# io.net
KiCad netlist of a schematic drawn in Altium Designer
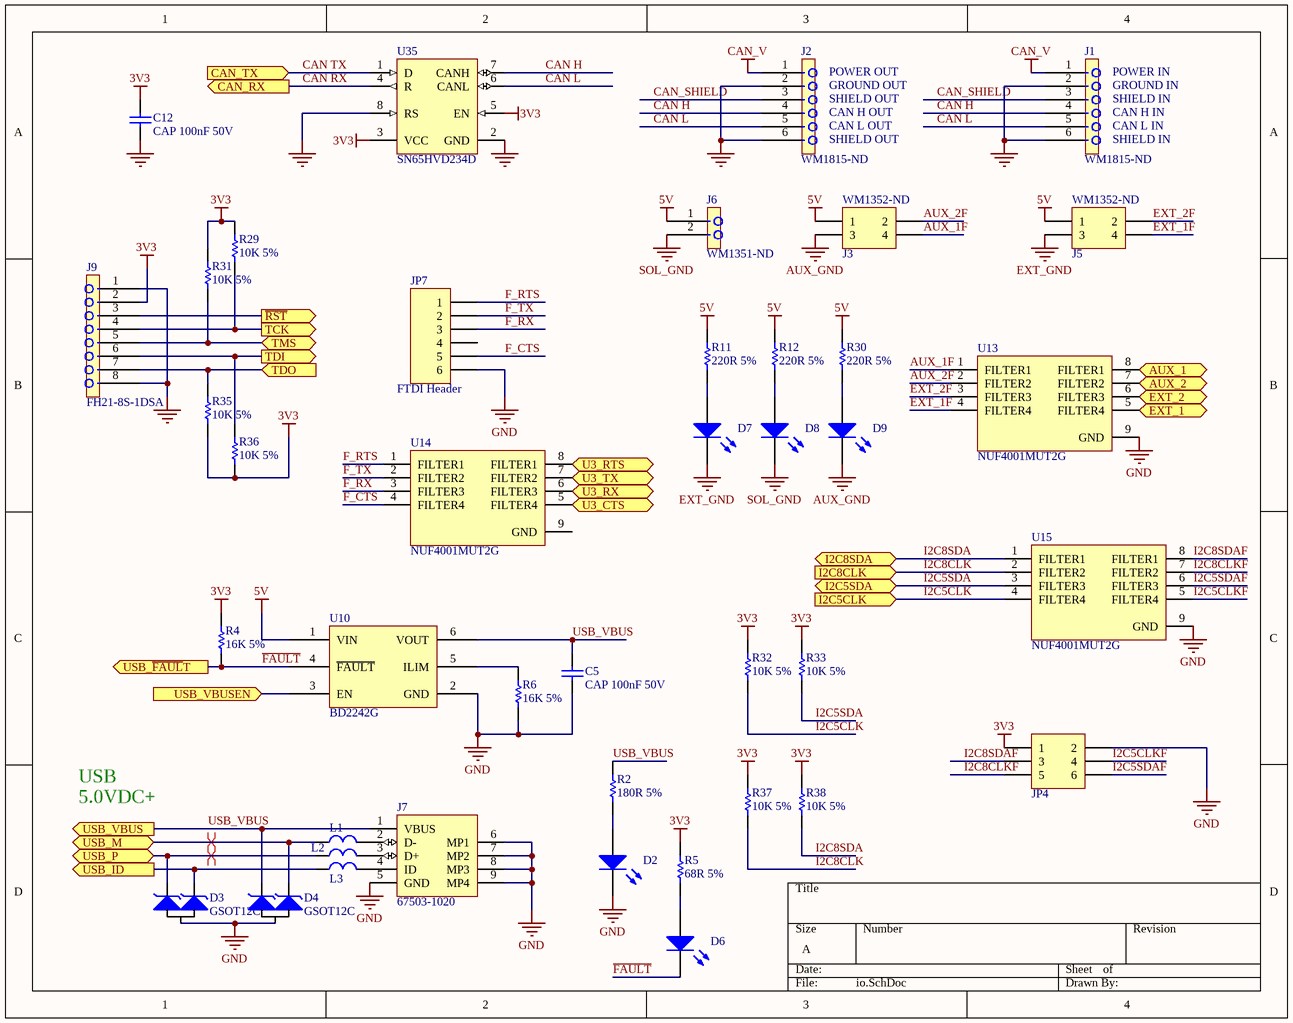
[diagram p0: io.SchDoc]

(export (version "E")
  (design (tool "Eeschema 10.0.6"))
  (components
    (comp (ref "C5")
      (value "CAP 100nF 50V")
      (footprint "CAPC0603(1608)100_M")
      (description "CAP 100nF 50V Â±0.1pF 0603 (1608 Metric) Thickness 1mm SMD")
      (fields (field (name "TOLERANCE") "Â±0.1pF"))
      (libsource (lib "Altium Content Vault") (part "CMP-1035-00010-1"))
    )
    (comp (ref "C12")
      (value "CAP 100nF 50V")
      (footprint "CAPC0603(1608)100_M")
      (description "CAP 100nF 50V Â±0.1pF 0603 (1608 Metric) Thickness 1mm SMD")
      (fields (field (name "TOLERANCE") "Â±0.1pF"))
      (libsource (lib "Altium Content Vault") (part "CMP-1035-00010-1"))
    )
    (comp (ref "D2")
      (value "LED")
      (footprint "LED-0603")
      (description "Typical RED, GREEN, YELLOW, AMBER GaAs LED")
      (fields (field (name "PUBLISHER") "Altium Limited"))
      (libsource (lib "HSBNE-Vend") (part "LED"))
    )
    (comp (ref "D3")
      (value "GSOT12C")
      (footprint "SOT-23 - ESD")
      (description "DIO GSOT12C ESD 2LINE 12V SOT23")
      (fields (field (name "MPN") "GSOT12C-E3-08"))
      (libsource (lib "HSBNE-Vend") (part "2749"))
    )
    (comp (ref "D4")
      (value "GSOT12C")
      (footprint "SOT-23 - ESD")
      (description "DIO GSOT12C ESD 2LINE 12V SOT23")
      (fields (field (name "MPN") "GSOT12C-E3-08"))
      (libsource (lib "HSBNE-Vend") (part "2749"))
    )
    (comp (ref "D6")
      (value "LED")
      (footprint "LED-0603")
      (description "Typical RED, GREEN, YELLOW, AMBER GaAs LED")
      (fields (field (name "PUBLISHER") "Altium Limited"))
      (libsource (lib "HSBNE-Vend") (part "LED"))
    )
    (comp (ref "D7")
      (value "LED")
      (footprint "LED-0603")
      (description "Typical RED, GREEN, YELLOW, AMBER GaAs LED")
      (fields (field (name "PUBLISHER") "Altium Limited"))
      (libsource (lib "HSBNE-Vend") (part "LED"))
    )
    (comp (ref "D8")
      (value "LED")
      (footprint "LED-0603")
      (description "Typical RED, GREEN, YELLOW, AMBER GaAs LED")
      (fields (field (name "PUBLISHER") "Altium Limited"))
      (libsource (lib "HSBNE-Vend") (part "LED"))
    )
    (comp (ref "D9")
      (value "LED")
      (footprint "LED-0603")
      (description "Typical RED, GREEN, YELLOW, AMBER GaAs LED")
      (fields (field (name "PUBLISHER") "Altium Limited"))
      (libsource (lib "HSBNE-Vend") (part "LED"))
    )
    (comp (ref "J1") (value "WM1815-ND") (footprint "M43045H-6") (libsource (lib "HSBNE-Vend") (part "CON6")))
    (comp (ref "J2") (value "WM1815-ND") (footprint "M43045H-6") (libsource (lib "HSBNE-Vend") (part "CON6")))
    (comp (ref "J3")
      (value "Header 2x2 2.54mm")
      (footprint "Molex 39-30-1040")
      (description "Header, 4-Pin")
      (fields (field (name "SUPPLIER PART NUMBER 1") "WM1352-ND"))
      (libsource (lib "HSBNE-Vend") (part "Header 2x2"))
    )
    (comp (ref "J5")
      (value "Header 2x2 2.54mm")
      (footprint "Molex 39-30-1040")
      (description "Header, 4-Pin")
      (fields (field (name "SUPPLIER PART NUMBER 1") "WM1352-ND"))
      (libsource (lib "HSBNE-Vend") (part "Header 2x2"))
    )
    (comp (ref "J6")
      (value "WM1351-ND")
      (footprint "M5569-2")
      (description "6.35mm right-angle 90° male spade terminal PCB mount")
      (libsource (lib "HSBNE-Vend") (part "CON2"))
    )
    (comp (ref "J7")
      (value "67503-1020")
      (footprint "MOLX-67503-1020_V")
      (description "USB, MINI, SMD, RA KME04-USBMU03A01")
      (fields (field (name "MANUFACTURER") "Molex"))
      (libsource (lib "Altium Content Vault") (part "MOLX-67503-1020"))
    )
    (comp (ref "J9")
      (value "FH21-8S-1DSA")
      (footprint "FH21-8S-1DSA")
      (libsource (lib "HSBNE-Vend") (part "CON8"))
    )
    (comp (ref "JP4")
      (value "Header 3x2 2.54mm")
      (footprint "2X3")
      (description "Header, 6-Pin")
      (libsource (lib "HSBNE-Vend") (part "Header 3x2"))
    )
    (comp (ref "JP7")
      (value "FTDI Header")
      (footprint "1X6")
      (description "Header, 6-Pin")
      (libsource (lib "snarc+3") (part "Header 6"))
    )
    (comp (ref "L1")
      (value "MPZ1608S102A")
      (footprint "0603")
      (description "IND FERRITE CHIP BEAD 1000 OHM @ 100MHz 800mA 0603")
      (libsource (lib "LXPN") (part "2982"))
    )
    (comp (ref "L2")
      (value "MPZ1608S102A")
      (footprint "0603")
      (description "IND FERRITE CHIP BEAD 1000 OHM @ 100MHz 800mA 0603")
      (libsource (lib "LXPN") (part "2982"))
    )
    (comp (ref "L3")
      (value "MPZ1608S102A")
      (footprint "0603")
      (description "IND FERRITE CHIP BEAD 1000 OHM @ 100MHz 800mA 0603")
      (libsource (lib "LXPN") (part "2982"))
    )
    (comp (ref "R2")
      (value "180R 5%")
      (footprint "RESC0603(1608)_L")
      (description "180R 0.1W 5% 0603 (1608 Metric)  SMD")
      (fields (field (name "POWER") "0.1 W") (field (name "TOLERANCE") "5 %"))
      (libsource (lib "Altium Content Vault") (part "CMP-1012-00056-1"))
    )
    (comp (ref "R4")
      (value "16K 5%")
      (footprint "RESC0603(1608)_L")
      (description "16K 0.1W 5% 0603 (1608 Metric)  SMD")
      (fields (field (name "TOLERANCE") "5 %") (field (name "POWER") "0.1 W"))
      (libsource (lib "Altium Content Vault") (part "RES"))
    )
    (comp (ref "R5")
      (value "68R 5%")
      (footprint "RESC0603(1608)_M")
      (description "68R 0.1W 5% 0603 (1608 Metric)  SMD")
      (fields (field (name "POWER") "0.1 W") (field (name "TOLERANCE") "5 %"))
      (libsource (lib "Altium Content Vault") (part "CMP-1012-00046-1"))
    )
    (comp (ref "R6")
      (value "16K 5%")
      (footprint "RESC0603(1608)_L")
      (description "16K 0.1W 5% 0603 (1608 Metric)  SMD")
      (fields (field (name "TOLERANCE") "5 %") (field (name "POWER") "0.1 W"))
      (libsource (lib "Altium Content Vault") (part "RES"))
    )
    (comp (ref "R11")
      (value "220R 5%")
      (footprint "RESC0603(1608)_M")
      (description "220R 0.1W 5% 0603 (1608 Metric)  SMD")
      (fields (field (name "POWER") "0.1 W") (field (name "TOLERANCE") "5 %"))
      (libsource (lib "Altium Content Vault") (part "CMP-1012-00058-1"))
    )
    (comp (ref "R12")
      (value "220R 5%")
      (footprint "RESC0603(1608)_M")
      (description "220R 0.1W 5% 0603 (1608 Metric)  SMD")
      (fields (field (name "POWER") "0.1 W") (field (name "TOLERANCE") "5 %"))
      (libsource (lib "Altium Content Vault") (part "CMP-1012-00058-1"))
    )
    (comp (ref "R29")
      (value "10K 5%")
      (footprint "RESC0603(1608)_N")
      (description "10K 0.1W 5% 0603 (1608 Metric)  SMD")
      (fields (field (name "TOLERANCE") "5 %") (field (name "POWER") "0.1 W"))
      (libsource (lib "Altium Content Vault") (part "RES"))
    )
    (comp (ref "R30")
      (value "220R 5%")
      (footprint "RESC0603(1608)_M")
      (description "220R 0.1W 5% 0603 (1608 Metric)  SMD")
      (fields (field (name "POWER") "0.1 W") (field (name "TOLERANCE") "5 %"))
      (libsource (lib "Altium Content Vault") (part "CMP-1012-00058-1"))
    )
    (comp (ref "R31")
      (value "10K 5%")
      (footprint "RESC0603(1608)_N")
      (description "10K 0.1W 5% 0603 (1608 Metric)  SMD")
      (fields (field (name "TOLERANCE") "5 %") (field (name "POWER") "0.1 W"))
      (libsource (lib "Altium Content Vault") (part "RES"))
    )
    (comp (ref "R32")
      (value "10K 5%")
      (footprint "RESC0603(1608)_N")
      (description "10K 0.1W 5% 0603 (1608 Metric)  SMD")
      (fields (field (name "TOLERANCE") "5 %") (field (name "POWER") "0.1 W"))
      (libsource (lib "Altium Content Vault") (part "RES"))
    )
    (comp (ref "R33")
      (value "10K 5%")
      (footprint "RESC0603(1608)_N")
      (description "10K 0.1W 5% 0603 (1608 Metric)  SMD")
      (fields (field (name "TOLERANCE") "5 %") (field (name "POWER") "0.1 W"))
      (libsource (lib "Altium Content Vault") (part "RES"))
    )
    (comp (ref "R35")
      (value "10K 5%")
      (footprint "RESC0603(1608)_N")
      (description "10K 0.1W 5% 0603 (1608 Metric)  SMD")
      (fields (field (name "TOLERANCE") "5 %") (field (name "POWER") "0.1 W"))
      (libsource (lib "Altium Content Vault") (part "RES"))
    )
    (comp (ref "R36")
      (value "10K 5%")
      (footprint "RESC0603(1608)_N")
      (description "10K 0.1W 5% 0603 (1608 Metric)  SMD")
      (fields (field (name "TOLERANCE") "5 %") (field (name "POWER") "0.1 W"))
      (libsource (lib "Altium Content Vault") (part "RES"))
    )
    (comp (ref "R37")
      (value "10K 5%")
      (footprint "RESC0603(1608)_N")
      (description "10K 0.1W 5% 0603 (1608 Metric)  SMD")
      (fields (field (name "TOLERANCE") "5 %") (field (name "POWER") "0.1 W"))
      (libsource (lib "Altium Content Vault") (part "RES"))
    )
    (comp (ref "R38")
      (value "10K 5%")
      (footprint "RESC0603(1608)_N")
      (description "10K 0.1W 5% 0603 (1608 Metric)  SMD")
      (fields (field (name "TOLERANCE") "5 %") (field (name "POWER") "0.1 W"))
      (libsource (lib "Altium Content Vault") (part "RES"))
    )
    (comp (ref "U10")
      (value "BD2242G")
      (footprint "SOT23-6")
      (description "BD2242G-GTR")
      (libsource (lib "HSBNE-Vend") (part "RT9728A"))
    )
    (comp (ref "U13")
      (value "NUF4001MUT2G")
      (footprint "ONSC-UDFN-8-517AD_V")
      (fields (field (name "MANUFACTURER") "On Semiconductor"))
      (libsource (lib "Altium Content Vault") (part "ONSC-EMI-NUF4XXXMX-8"))
    )
    (comp (ref "U14")
      (value "NUF4001MUT2G")
      (footprint "ONSC-UDFN-8-517AD_V")
      (fields (field (name "MANUFACTURER") "On Semiconductor"))
      (libsource (lib "Altium Content Vault") (part "ONSC-EMI-NUF4XXXMX-8"))
    )
    (comp (ref "U15")
      (value "NUF4001MUT2G")
      (footprint "ONSC-UDFN-8-517AD_V")
      (fields (field (name "MANUFACTURER") "On Semiconductor"))
      (libsource (lib "Altium Content Vault") (part "ONSC-EMI-NUF4XXXMX-8"))
    )
    (comp (ref "U35")
      (value "SN65HVD234D")
      (footprint "D8_M")
      (fields (field (name "MANUFACTURER") "Texas Instruments"))
      (libsource (lib "Altium Content Vault") (part "TI-SN65HVD234-SOIC_D-8"))
    )
  )
  (nets
    (net (code "1") (name "/AUX_1") (class "Default")
      (node (ref "U13") (pin "8") (pinfunction "FILTER1_8") (pintype "passive"))
    )
    (net (code "2") (name "/AUX_1F") (class "Default")
      (node (ref "J3") (pin "4") (pinfunction "4_4") (pintype "passive"))
      (node (ref "U13") (pin "1") (pinfunction "FILTER1_1") (pintype "passive"))
    )
    (net (code "3") (name "/AUX_2") (class "Default")
      (node (ref "U13") (pin "7") (pinfunction "FILTER2_7") (pintype "passive"))
    )
    (net (code "4") (name "/AUX_2F") (class "Default")
      (node (ref "J3") (pin "2") (pinfunction "2_2") (pintype "passive"))
      (node (ref "U13") (pin "2") (pinfunction "FILTER2_2") (pintype "passive"))
    )
    (net (code "5") (name "/CAN H") (class "Default")
      (node (ref "J1") (pin "4") (pintype "passive"))
      (node (ref "J2") (pin "4") (pintype "passive"))
      (node (ref "U35") (pin "7") (pinfunction "CANH_7") (pintype "bidirectional"))
    )
    (net (code "6") (name "/CAN L") (class "Default")
      (node (ref "J1") (pin "5") (pintype "passive"))
      (node (ref "J2") (pin "5") (pintype "passive"))
      (node (ref "U35") (pin "6") (pinfunction "CANL_6") (pintype "bidirectional"))
    )
    (net (code "7") (name "/CAN RX") (class "Default")
      (node (ref "U35") (pin "4") (pinfunction "R_4") (pintype "output"))
    )
    (net (code "8") (name "/CAN TX") (class "Default")
      (node (ref "U35") (pin "1") (pinfunction "D_1") (pintype "input"))
    )
    (net (code "9") (name "/CAN_SHIELD") (class "Default")
      (node (ref "J1") (pin "3") (pintype "passive"))
      (node (ref "J2") (pin "3") (pintype "passive"))
    )
    (net (code "10") (name "/EXT_1") (class "Default")
      (node (ref "U13") (pin "5") (pinfunction "FILTER4_5") (pintype "passive"))
    )
    (net (code "11") (name "/EXT_1F") (class "Default")
      (node (ref "J5") (pin "4") (pinfunction "4_4") (pintype "passive"))
      (node (ref "U13") (pin "4") (pinfunction "FILTER4_4") (pintype "passive"))
    )
    (net (code "12") (name "/EXT_2") (class "Default")
      (node (ref "U13") (pin "6") (pinfunction "FILTER3_6") (pintype "passive"))
    )
    (net (code "13") (name "/EXT_2F") (class "Default")
      (node (ref "J5") (pin "2") (pinfunction "2_2") (pintype "passive"))
      (node (ref "U13") (pin "3") (pinfunction "FILTER3_3") (pintype "passive"))
    )
    (net (code "14") (name "/F_CTS") (class "Default")
      (node (ref "JP7") (pin "5") (pinfunction "5_5") (pintype "passive"))
      (node (ref "U14") (pin "4") (pinfunction "FILTER4_4") (pintype "passive"))
    )
    (net (code "15") (name "/F_RTS") (class "Default")
      (node (ref "JP7") (pin "1") (pinfunction "1_1") (pintype "passive"))
      (node (ref "U14") (pin "1") (pinfunction "FILTER1_1") (pintype "passive"))
    )
    (net (code "16") (name "/F_RX") (class "Default")
      (node (ref "JP7") (pin "3") (pinfunction "3_3") (pintype "passive"))
      (node (ref "U14") (pin "3") (pinfunction "FILTER3_3") (pintype "passive"))
    )
    (net (code "17") (name "/F_TX") (class "Default")
      (node (ref "JP7") (pin "2") (pinfunction "2_2") (pintype "passive"))
      (node (ref "U14") (pin "2") (pinfunction "FILTER2_2") (pintype "passive"))
    )
    (net (code "18") (name "/I2C5CLK") (class "Default")
      (node (ref "R32") (pin "1") (pinfunction "1_1") (pintype "passive"))
      (node (ref "U15") (pin "4") (pinfunction "FILTER4_4") (pintype "passive"))
    )
    (net (code "19") (name "/I2C5CLKF") (class "Default")
      (node (ref "JP4") (pin "4") (pinfunction "4_4") (pintype "passive"))
      (node (ref "U15") (pin "5") (pinfunction "FILTER4_5") (pintype "passive"))
    )
    (net (code "20") (name "/I2C5SDA") (class "Default")
      (node (ref "R33") (pin "1") (pinfunction "1_1") (pintype "passive"))
      (node (ref "U15") (pin "3") (pinfunction "FILTER3_3") (pintype "passive"))
    )
    (net (code "21") (name "/I2C5SDAF") (class "Default")
      (node (ref "JP4") (pin "6") (pinfunction "6_6") (pintype "passive"))
      (node (ref "U15") (pin "6") (pinfunction "FILTER3_6") (pintype "passive"))
    )
    (net (code "22") (name "/I2C8CLK") (class "Default")
      (node (ref "R37") (pin "1") (pinfunction "1_1") (pintype "passive"))
      (node (ref "U15") (pin "2") (pinfunction "FILTER2_2") (pintype "passive"))
    )
    (net (code "23") (name "/I2C8CLKF") (class "Default")
      (node (ref "JP4") (pin "5") (pinfunction "5_5") (pintype "passive"))
      (node (ref "U15") (pin "7") (pinfunction "FILTER2_7") (pintype "passive"))
    )
    (net (code "24") (name "/I2C8SDA") (class "Default")
      (node (ref "R38") (pin "1") (pinfunction "1_1") (pintype "passive"))
      (node (ref "U15") (pin "1") (pinfunction "FILTER1_1") (pintype "passive"))
    )
    (net (code "25") (name "/I2C8SDAF") (class "Default")
      (node (ref "JP4") (pin "3") (pinfunction "3_3") (pintype "passive"))
      (node (ref "U15") (pin "8") (pinfunction "FILTER1_8") (pintype "passive"))
    )
    (net (code "26") (name "/TCK") (class "Default")
      (node (ref "J9") (pin "4") (pintype "passive"))
      (node (ref "R29") (pin "1") (pinfunction "1_1") (pintype "passive"))
    )
    (net (code "27") (name "/TDI") (class "Default")
      (node (ref "J9") (pin "6") (pintype "passive"))
      (node (ref "R36") (pin "2") (pinfunction "2_2") (pintype "passive"))
    )
    (net (code "28") (name "/TDO") (class "Default")
      (node (ref "J9") (pin "7") (pintype "passive"))
      (node (ref "R35") (pin "2") (pinfunction "2_2") (pintype "passive"))
    )
    (net (code "29") (name "/TMS") (class "Default")
      (node (ref "J9") (pin "5") (pintype "passive"))
      (node (ref "R31") (pin "1") (pinfunction "1_1") (pintype "passive"))
    )
    (net (code "30") (name "/U3_CTS") (class "Default")
      (node (ref "U14") (pin "5") (pinfunction "FILTER4_5") (pintype "passive"))
    )
    (net (code "31") (name "/U3_RTS") (class "Default")
      (node (ref "U14") (pin "8") (pinfunction "FILTER1_8") (pintype "passive"))
    )
    (net (code "32") (name "/U3_RX") (class "Default")
      (node (ref "U14") (pin "6") (pinfunction "FILTER3_6") (pintype "passive"))
    )
    (net (code "33") (name "/U3_TX") (class "Default")
      (node (ref "U14") (pin "7") (pinfunction "FILTER2_7") (pintype "passive"))
    )
    (net (code "34") (name "/USB_ID") (class "Default")
      (node (ref "D3") (pin "2") (pinfunction "K2_2") (pintype "passive"))
      (node (ref "L3") (pin "1") (pinfunction "1_1") (pintype "passive"))
    )
    (net (code "35") (name "/USB_M") (class "Default")
      (node (ref "D4") (pin "2") (pinfunction "K2_2") (pintype "passive"))
      (node (ref "L1") (pin "1") (pinfunction "1_1") (pintype "passive"))
    )
    (net (code "36") (name "/USB_P") (class "Default")
      (node (ref "D3") (pin "1") (pinfunction "K1_1") (pintype "passive"))
      (node (ref "L2") (pin "1") (pinfunction "1_1") (pintype "passive"))
    )
    (net (code "37") (name "/USB_VBUS") (class "Default")
      (node (ref "C5") (pin "2") (pinfunction "2_2") (pintype "passive"))
      (node (ref "D4") (pin "1") (pinfunction "K1_1") (pintype "passive"))
      (node (ref "J7") (pin "1") (pinfunction "VBUS_1") (pintype "power_in"))
      (node (ref "R2") (pin "2") (pinfunction "2_2") (pintype "passive"))
      (node (ref "U10") (pin "6") (pinfunction "VOUT_6") (pintype "passive"))
    )
    (net (code "38") (name "/USB_VBUSEN") (class "Default")
      (node (ref "U10") (pin "3") (pinfunction "EN_3") (pintype "passive"))
    )
    (net (code "39") (name "/~{FAULT}") (class "Default")
      (node (ref "D6") (pin "2") (pinfunction "K_2") (pintype "passive"))
      (node (ref "R4") (pin "1") (pinfunction "1_1") (pintype "passive"))
      (node (ref "U10") (pin "4") (pinfunction "~{FAULT}_4") (pintype "passive"))
    )
    (net (code "40") (name "/~{RST}") (class "Default") (node (ref "J9") (pin "3") (pintype "passive")))
    (net (code "41") (name "3V3") (class "Default")
      (node (ref "C12") (pin "2") (pinfunction "2_2") (pintype "passive"))
      (node (ref "J9") (pin "2") (pintype "passive"))
      (node (ref "JP4") (pin "1") (pinfunction "1_1") (pintype "passive"))
      (node (ref "R29") (pin "2") (pinfunction "2_2") (pintype "passive"))
      (node (ref "R31") (pin "2") (pinfunction "2_2") (pintype "passive"))
      (node (ref "R32") (pin "2") (pinfunction "2_2") (pintype "passive"))
      (node (ref "R33") (pin "2") (pinfunction "2_2") (pintype "passive"))
      (node (ref "R35") (pin "1") (pinfunction "1_1") (pintype "passive"))
      (node (ref "R36") (pin "1") (pinfunction "1_1") (pintype "passive"))
      (node (ref "R37") (pin "2") (pinfunction "2_2") (pintype "passive"))
      (node (ref "R38") (pin "2") (pinfunction "2_2") (pintype "passive"))
      (node (ref "R4") (pin "2") (pinfunction "2_2") (pintype "passive"))
      (node (ref "R5") (pin "2") (pinfunction "2_2") (pintype "passive"))
      (node (ref "U35") (pin "3") (pinfunction "VCC_3") (pintype "power_in"))
      (node (ref "U35") (pin "5") (pinfunction "EN_5") (pintype "input"))
    )
    (net (code "42") (name "5V") (class "Default")
      (node (ref "J3") (pin "1") (pinfunction "1_1") (pintype "passive"))
      (node (ref "J5") (pin "1") (pinfunction "1_1") (pintype "passive"))
      (node (ref "J6") (pin "1") (pintype "passive"))
      (node (ref "R11") (pin "2") (pinfunction "2_2") (pintype "passive"))
      (node (ref "R12") (pin "2") (pinfunction "2_2") (pintype "passive"))
      (node (ref "R30") (pin "2") (pinfunction "2_2") (pintype "passive"))
      (node (ref "U10") (pin "1") (pinfunction "VIN_1") (pintype "passive"))
    )
    (net (code "43") (name "AUX_GND") (class "Default")
      (node (ref "D9") (pin "2") (pinfunction "K_2") (pintype "passive"))
      (node (ref "J3") (pin "3") (pinfunction "3_3") (pintype "passive"))
    )
    (net (code "44") (name "CAN_V") (class "Default")
      (node (ref "J1") (pin "1") (pintype "passive"))
      (node (ref "J2") (pin "1") (pintype "passive"))
    )
    (net (code "45") (name "EXT_GND") (class "Default")
      (node (ref "D7") (pin "2") (pinfunction "K_2") (pintype "passive"))
      (node (ref "J5") (pin "3") (pinfunction "3_3") (pintype "passive"))
    )
    (net (code "46") (name "GND") (class "Default")
      (node (ref "C12") (pin "1") (pinfunction "1_1") (pintype "passive"))
      (node (ref "C5") (pin "1") (pinfunction "1_1") (pintype "passive"))
      (node (ref "D2") (pin "2") (pinfunction "K_2") (pintype "passive"))
      (node (ref "D3") (pin "3") (pinfunction "A_3") (pintype "passive"))
      (node (ref "D4") (pin "3") (pinfunction "A_3") (pintype "passive"))
      (node (ref "J1") (pin "2") (pintype "passive"))
      (node (ref "J1") (pin "6") (pintype "passive"))
      (node (ref "J2") (pin "2") (pintype "passive"))
      (node (ref "J2") (pin "6") (pintype "passive"))
      (node (ref "J7") (pin "5") (pinfunction "GND_5") (pintype "power_in"))
      (node (ref "J7") (pin "6") (pinfunction "MP1_6") (pintype "passive"))
      (node (ref "J7") (pin "7") (pinfunction "MP2_7") (pintype "passive"))
      (node (ref "J7") (pin "8") (pinfunction "MP3_8") (pintype "passive"))
      (node (ref "J7") (pin "9") (pinfunction "MP4_9") (pintype "passive"))
      (node (ref "J9") (pin "1") (pintype "passive"))
      (node (ref "J9") (pin "8") (pintype "passive"))
      (node (ref "JP4") (pin "2") (pinfunction "2_2") (pintype "passive"))
      (node (ref "JP7") (pin "6") (pinfunction "6_6") (pintype "passive"))
      (node (ref "R6") (pin "1") (pinfunction "1_1") (pintype "passive"))
      (node (ref "U10") (pin "2") (pinfunction "GND_2") (pintype "passive"))
      (node (ref "U13") (pin "9") (pinfunction "GND_9") (pintype "power_in"))
      (node (ref "U15") (pin "9") (pinfunction "GND_9") (pintype "power_in"))
      (node (ref "U35") (pin "2") (pinfunction "GND_2") (pintype "power_in"))
      (node (ref "U35") (pin "8") (pinfunction "RS_8") (pintype "input"))
    )
    (net (code "47") (name "Net-(D2-A)") (class "Default")
      (node (ref "D2") (pin "1") (pinfunction "A_1") (pintype "passive"))
      (node (ref "R2") (pin "1") (pinfunction "1_1") (pintype "passive"))
    )
    (net (code "48") (name "Net-(D6-A)") (class "Default")
      (node (ref "D6") (pin "1") (pinfunction "A_1") (pintype "passive"))
      (node (ref "R5") (pin "1") (pinfunction "1_1") (pintype "passive"))
    )
    (net (code "49") (name "Net-(D7-A)") (class "Default")
      (node (ref "D7") (pin "1") (pinfunction "A_1") (pintype "passive"))
      (node (ref "R11") (pin "1") (pinfunction "1_1") (pintype "passive"))
    )
    (net (code "50") (name "Net-(D8-A)") (class "Default")
      (node (ref "D8") (pin "1") (pinfunction "A_1") (pintype "passive"))
      (node (ref "R12") (pin "1") (pinfunction "1_1") (pintype "passive"))
    )
    (net (code "51") (name "Net-(D9-A)") (class "Default")
      (node (ref "D9") (pin "1") (pinfunction "A_1") (pintype "passive"))
      (node (ref "R30") (pin "1") (pinfunction "1_1") (pintype "passive"))
    )
    (net (code "52") (name "Net-(J7-D+)") (class "Default")
      (node (ref "J7") (pin "3") (pinfunction "D+_3") (pintype "bidirectional"))
      (node (ref "L2") (pin "2") (pinfunction "2_2") (pintype "passive"))
    )
    (net (code "53") (name "Net-(J7-D-)") (class "Default")
      (node (ref "J7") (pin "2") (pinfunction "D-_2") (pintype "bidirectional"))
      (node (ref "L1") (pin "2") (pinfunction "2_2") (pintype "passive"))
    )
    (net (code "54") (name "Net-(J7-ID)") (class "Default")
      (node (ref "J7") (pin "4") (pinfunction "ID_4") (pintype "passive"))
      (node (ref "L3") (pin "2") (pinfunction "2_2") (pintype "passive"))
    )
    (net (code "55") (name "Net-(U10-ILIM)") (class "Default")
      (node (ref "R6") (pin "2") (pinfunction "2_2") (pintype "passive"))
      (node (ref "U10") (pin "5") (pinfunction "ILIM_5") (pintype "passive"))
    )
    (net (code "56") (name "SOL_GND") (class "Default")
      (node (ref "D8") (pin "2") (pinfunction "K_2") (pintype "passive"))
      (node (ref "J6") (pin "2") (pintype "passive"))
    )
    (net (code "57") (name "unconnected-(JP7-Pad4)") (class "Default")
      (node (ref "JP7") (pin "4") (pinfunction "4_4") (pintype "passive"))
    )
    (net (code "58") (name "unconnected-(U14-GND-Pad9)") (class "Default")
      (node (ref "U14") (pin "9") (pinfunction "GND_9") (pintype "power_in"))
    )
  )
)
